# LIS331DLH.net
KiCad netlist of a schematic drawn in EAGLE
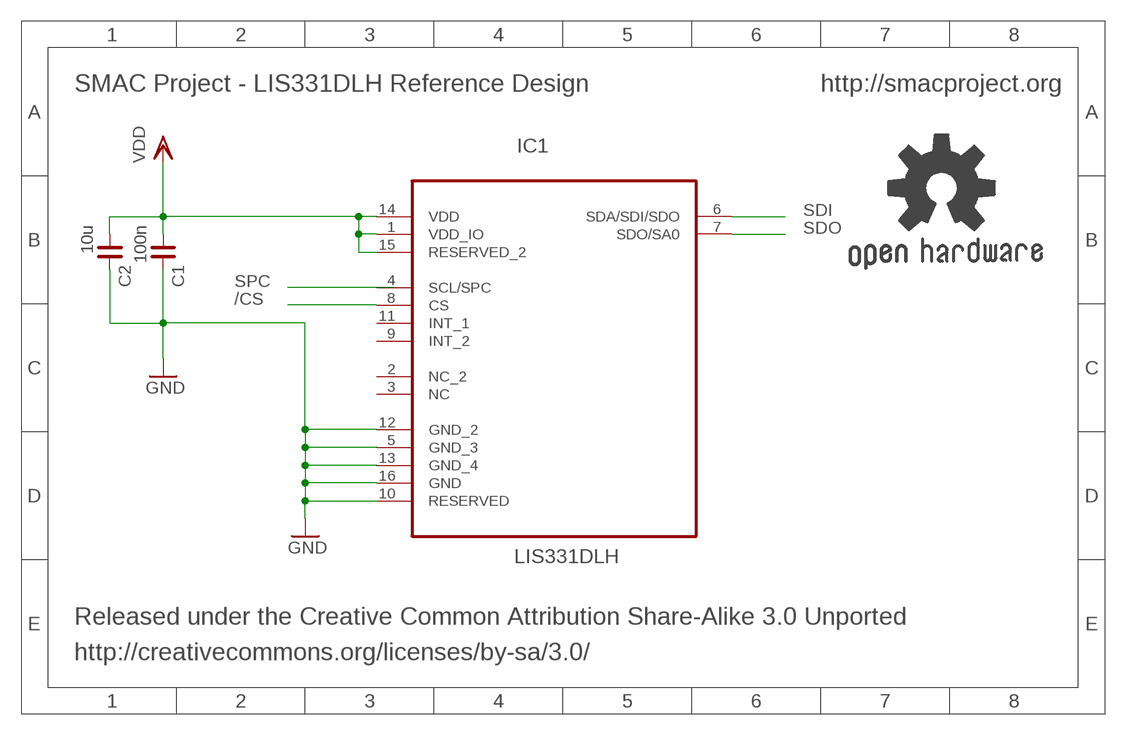
[diagram p0: schematic, sheet 1]

(export (version "E")
  (design (tool "Eeschema 10.0.6"))
  (components
    (comp (ref "C1")
      (value "100n")
      (footprint "eagle-import:C0402")
      (libsource (lib "eagle-import") (part "C_0402"))
    )
    (comp (ref "C2")
      (value "10u")
      (footprint "eagle-import:C0402")
      (libsource (lib "eagle-import") (part "C_0402"))
    )
    (comp (ref "GOLD_ORB_SM2")
      (value "OSHWLOGO_REF_SM")
      (footprint "eagle-import:OSHW2REF")
      (libsource (lib "eagle-import") (part "OSHWLOGO_REF_SM"))
    )
    (comp (ref "IC1")
      (value "LIS331DLH")
      (footprint "eagle-import:LGA16R50P3X5_300X300X100")
      (libsource (lib "eagle-import") (part "LIS331DLH"))
    )
  )
  (nets
    (net (code "1") (name "/SDI") (class "Default")
      (node (ref "IC1") (pin "6") (pinfunction "SDA/SDI/SDO_6") (pintype "bidirectional"))
    )
    (net (code "2") (name "/SDO") (class "Default")
      (node (ref "IC1") (pin "7") (pinfunction "SDO/SA0_7") (pintype "output"))
    )
    (net (code "3") (name "/SPC") (class "Default")
      (node (ref "IC1") (pin "4") (pinfunction "SCL/SPC_4") (pintype "input"))
    )
    (net (code "4") (name "/{slash}CS") (class "Default")
      (node (ref "IC1") (pin "8") (pinfunction "CS_8") (pintype "input"))
    )
    (net (code "5") (name "GND") (class "Default")
      (node (ref "C1") (pin "2") (pinfunction "2_2") (pintype "passive"))
      (node (ref "C2") (pin "2") (pinfunction "2_2") (pintype "passive"))
      (node (ref "IC1") (pin "10") (pinfunction "RESERVED_10") (pintype "passive"))
      (node (ref "IC1") (pin "12") (pinfunction "GND_2_12") (pintype "passive"))
      (node (ref "IC1") (pin "13") (pinfunction "GND_4_13") (pintype "passive"))
      (node (ref "IC1") (pin "16") (pinfunction "GND_16") (pintype "passive"))
      (node (ref "IC1") (pin "5") (pinfunction "GND_3_5") (pintype "passive"))
    )
    (net (code "6") (name "VDD") (class "Default")
      (node (ref "C1") (pin "1") (pinfunction "1_1") (pintype "passive"))
      (node (ref "C2") (pin "1") (pinfunction "1_1") (pintype "passive"))
      (node (ref "IC1") (pin "1") (pinfunction "VDD_IO_1") (pintype "power_in"))
      (node (ref "IC1") (pin "14") (pinfunction "VDD_14") (pintype "power_in"))
      (node (ref "IC1") (pin "15") (pinfunction "RESERVED_2_15") (pintype "power_in"))
    )
    (net (code "7") (name "unconnected-(IC1-INT_1-Pad11)") (class "Default")
      (node (ref "IC1") (pin "11") (pinfunction "INT_1_11") (pintype "input"))
    )
    (net (code "8") (name "unconnected-(IC1-INT_2-Pad9)") (class "Default")
      (node (ref "IC1") (pin "9") (pinfunction "INT_2_9") (pintype "input"))
    )
    (net (code "9") (name "unconnected-(IC1-NC-Pad3)") (class "Default")
      (node (ref "IC1") (pin "3") (pinfunction "NC_3") (pintype "no_connect"))
    )
    (net (code "10") (name "unconnected-(IC1-NC_2-Pad2)") (class "Default")
      (node (ref "IC1") (pin "2") (pinfunction "NC_2_2") (pintype "no_connect"))
    )
  )
)
